# switch.net
KiCad netlist of a schematic drawn in EAGLE
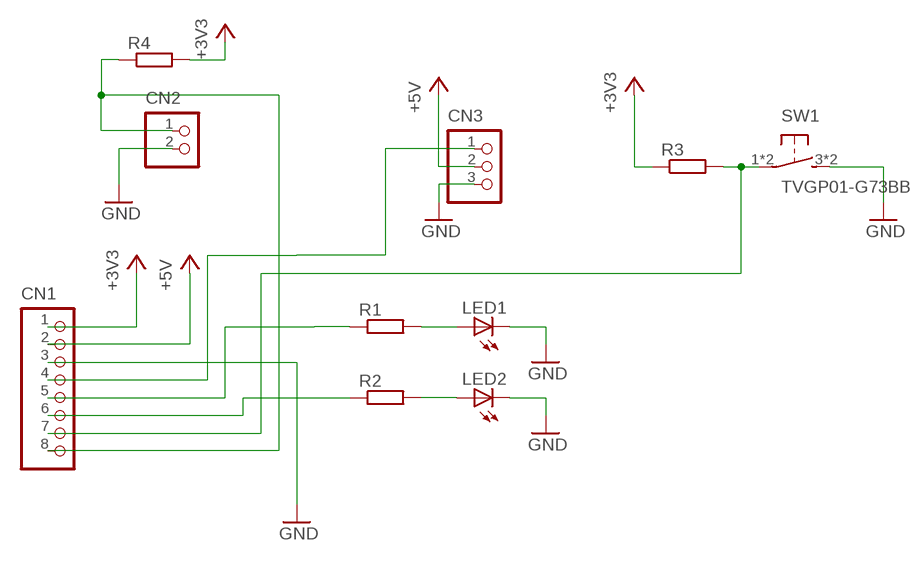
[diagram p0: schematic, sheet 1]

(export (version "E")
  (design (tool "Eeschema 10.0.6"))
  (components
    (comp (ref "CN1")
      (value "B8B-PH-K-S")
      (footprint "eagle-import:B8B-PH-K-S")
      (libsource (lib "eagle-import") (part "B8B-PH-K-S"))
    )
    (comp (ref "CN2")
      (value "B2B-PH-K-S")
      (footprint "eagle-import:B2B-PH-K-S")
      (libsource (lib "eagle-import") (part "B2B-PH-K-S"))
    )
    (comp (ref "CN3")
      (value "B3B-PH-K-S")
      (footprint "eagle-import:B3B-PH-K-S")
      (libsource (lib "eagle-import") (part "B3B-PH-K-S"))
    )
    (comp (ref "LED1")
      (value "LED5MM")
      (footprint "eagle-import:LED5MM")
      (libsource (lib "eagle-import") (part "LED5MM"))
    )
    (comp (ref "LED2")
      (value "LED5MM")
      (footprint "eagle-import:LED5MM")
      (libsource (lib "eagle-import") (part "LED5MM"))
    )
    (comp (ref "R1")
      (value "R-EU_0204/7")
      (footprint "eagle-import:0204_7")
      (libsource (lib "eagle-import") (part "R-EU_0204/7"))
    )
    (comp (ref "R2")
      (value "R-EU_0204/7")
      (footprint "eagle-import:0204_7")
      (libsource (lib "eagle-import") (part "R-EU_0204/7"))
    )
    (comp (ref "R3")
      (value "R-EU_0204/7")
      (footprint "eagle-import:0204_7")
      (libsource (lib "eagle-import") (part "R-EU_0204/7"))
    )
    (comp (ref "R4")
      (value "R-EU_0204/7")
      (footprint "eagle-import:0204_7")
      (libsource (lib "eagle-import") (part "R-EU_0204/7"))
    )
    (comp (ref "SW1")
      (value "TVGP01-G73BB")
      (footprint "eagle-import:TVGP01-G73BB")
      (libsource (lib "eagle-import") (part "TVGP01-G73BB"))
    )
  )
  (nets
    (net (code "1") (name "+3V3") (class "Default")
      (node (ref "CN1") (pin "1") (pinfunction "1_1") (pintype "passive"))
      (node (ref "R3") (pin "1") (pinfunction "1_1") (pintype "passive"))
      (node (ref "R4") (pin "2") (pinfunction "2_2") (pintype "passive"))
    )
    (net (code "2") (name "+5V") (class "Default")
      (node (ref "CN1") (pin "2") (pinfunction "2_2") (pintype "passive"))
      (node (ref "CN3") (pin "2") (pinfunction "2_2") (pintype "passive"))
    )
    (net (code "3") (name "GND") (class "Default")
      (node (ref "CN1") (pin "3") (pinfunction "3_3") (pintype "passive"))
      (node (ref "CN2") (pin "2") (pinfunction "2_2") (pintype "passive"))
      (node (ref "CN3") (pin "3") (pinfunction "3_3") (pintype "passive"))
      (node (ref "LED1") (pin "K") (pinfunction "C_K") (pintype "passive"))
      (node (ref "LED2") (pin "K") (pinfunction "C_K") (pintype "passive"))
      (node (ref "SW1") (pin "3") (pinfunction "2_3") (pintype "passive"))
      (node (ref "SW1") (pin "4") (pinfunction "2_4") (pintype "passive"))
    )
    (net (code "4") (name "Net-(CN1-Pad4)") (class "Default")
      (node (ref "CN1") (pin "4") (pinfunction "4_4") (pintype "passive"))
      (node (ref "CN3") (pin "1") (pinfunction "1_1") (pintype "passive"))
    )
    (net (code "5") (name "Net-(CN1-Pad5)") (class "Default")
      (node (ref "CN1") (pin "5") (pinfunction "5_5") (pintype "passive"))
      (node (ref "R1") (pin "1") (pinfunction "1_1") (pintype "passive"))
    )
    (net (code "6") (name "Net-(CN1-Pad6)") (class "Default")
      (node (ref "CN1") (pin "6") (pinfunction "6_6") (pintype "passive"))
      (node (ref "R2") (pin "1") (pinfunction "1_1") (pintype "passive"))
    )
    (net (code "7") (name "Net-(CN1-Pad7)") (class "Default")
      (node (ref "CN1") (pin "7") (pinfunction "7_7") (pintype "passive"))
      (node (ref "R3") (pin "2") (pinfunction "2_2") (pintype "passive"))
      (node (ref "SW1") (pin "1") (pinfunction "1_1") (pintype "passive"))
      (node (ref "SW1") (pin "2") (pinfunction "1_2") (pintype "passive"))
    )
    (net (code "8") (name "Net-(CN1-Pad8)") (class "Default")
      (node (ref "CN1") (pin "8") (pinfunction "8_8") (pintype "passive"))
      (node (ref "CN2") (pin "1") (pinfunction "1_1") (pintype "passive"))
      (node (ref "R4") (pin "1") (pinfunction "1_1") (pintype "passive"))
    )
    (net (code "9") (name "Net-(LED1-PadA)") (class "Default")
      (node (ref "LED1") (pin "A") (pinfunction "A_A") (pintype "passive"))
      (node (ref "R1") (pin "2") (pinfunction "2_2") (pintype "passive"))
    )
    (net (code "10") (name "Net-(LED2-PadA)") (class "Default")
      (node (ref "LED2") (pin "A") (pinfunction "A_A") (pintype "passive"))
      (node (ref "R2") (pin "2") (pinfunction "2_2") (pintype "passive"))
    )
  )
)
